# Power_Supply.net
KiCad netlist of a schematic drawn in Altium Designer
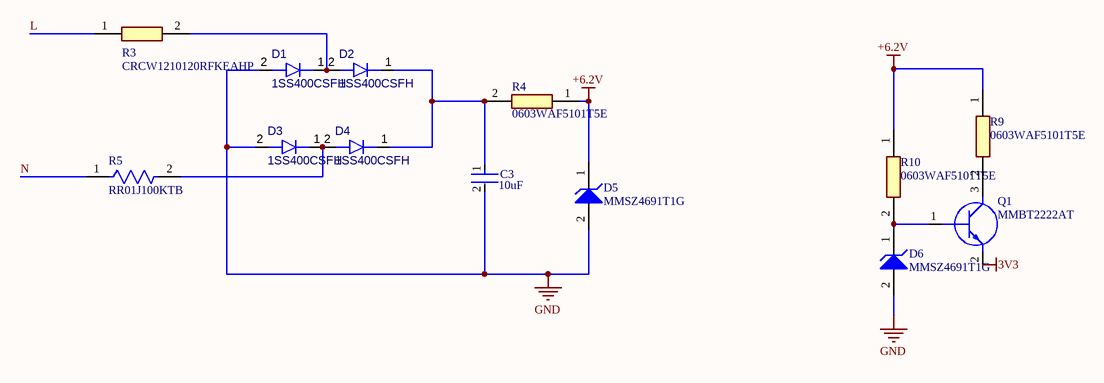
[diagram p0: Power Supply.SchDoc]

(export (version "E")
  (design (tool "Eeschema 10.0.6"))
  (components
    (comp (ref "C3")
      (value "1206YD106KAT2A")
      (footprint "FP-1206-L_3_2_0_2-W_1_6_0-IPC_B")
      (description "General Purpose Ceramic Capacitor, 1206, 10uF, 10%, X5R, 15%, 16V")
      (fields
        (field (name "TOLERANCE") "10%")
        (field (name "CAPACITANCE") "10uF")
        (field (name "VOLTAGE") "16V")
      )
      (libsource (lib "Altium Content Vault") (part "02cd4be3c70576c341d710602a673aa"))
    )
    (comp (ref "D1")
      (value "1SS400CSFH")
      (footprint "ROHM-VMN2-2_V")
      (description "Switching Diode (High Speed Switching), 80 V, 100 mA, 2-Pin SOD-923, RoHS, Tape and Reel")
      (libsource (lib "University of Moratuwa") (part "D-KA-2"))
    )
    (comp (ref "D2")
      (value "1SS400CSFH")
      (footprint "ROHM-VMN2-2_V")
      (description "Switching Diode (High Speed Switching), 80 V, 100 mA, 2-Pin SOD-923, RoHS, Tape and Reel")
      (libsource (lib "University of Moratuwa") (part "D-KA-2"))
    )
    (comp (ref "D3")
      (value "1SS400CSFH")
      (footprint "ROHM-VMN2-2_V")
      (description "Switching Diode (High Speed Switching), 80 V, 100 mA, 2-Pin SOD-923, RoHS, Tape and Reel")
      (libsource (lib "University of Moratuwa") (part "D-KA-2"))
    )
    (comp (ref "D4")
      (value "1SS400CSFH")
      (footprint "ROHM-VMN2-2_V")
      (description "Switching Diode (High Speed Switching), 80 V, 100 mA, 2-Pin SOD-923, RoHS, Tape and Reel")
      (libsource (lib "University of Moratuwa") (part "D-KA-2"))
    )
    (comp (ref "D5")
      (value "MMSZ4691T1G")
      (footprint "ONSC-SOD-123-2-425-04_V")
      (description "Zener Voltage Regulator, 500 mW, 2-Pin SOD-123, Pb-Free, Tape and Reel")
      (fields (field (name "MANUFACTURER") "On Semiconductor"))
      (libsource (lib "Altium Content Vault") (part "ONSC-K1A2-2"))
    )
    (comp (ref "D6")
      (value "MMSZ4691T1G")
      (footprint "ONSC-SOD-123-2-425-04_V")
      (description "Zener Voltage Regulator, 500 mW, 2-Pin SOD-123, Pb-Free, Tape and Reel")
      (fields (field (name "MANUFACTURER") "On Semiconductor"))
      (libsource (lib "Altium Content Vault") (part "ONSC-K1A2-2"))
    )
    (comp (ref "Q1")
      (value "MMBT2222AT")
      (footprint "SamacSys:SOTFL50P160X78-3N")
      (description "Transistor BJT NPN")
      (fields (field (name "MOUSER PART NUMBER") "512-MMBT2222AT"))
      (libsource (lib "*") (part "MMBT2222AT"))
    )
    (comp (ref "R3")
      (value "CRCW1210120RFKEAHP")
      (footprint "SamacSys:RESC3225X70N")
      (description "Resistor")
      (fields (field (name "MOUSER PART NUMBER") "71-CRCW1210120RFKEAH"))
      (libsource (lib "*") (part "CRCW1210120RFKEAHP"))
    )
    (comp (ref "R4")
      (value "0603WAF5101T5E")
      (footprint "SamacSys:RESC1608X55N")
      (description "Resistor")
      (libsource (lib "") (part "0603WAF5101T5E_1"))
    )
    (comp (ref "R5")
      (value "RR01J100KTB")
      (footprint "FP-RR01-MFG")
      (description "RES 100K OHM 5% 1W AXIAL")
      (fields (field (name "TOLERANCE") "5%"))
      (libsource (lib "Altium Content Vault") (part "1029c3af85768c4190bb7ad29bc67b5"))
    )
    (comp (ref "R9")
      (value "0603WAF5101T5E")
      (footprint "SamacSys:RESC1608X55N")
      (description "Resistor")
      (libsource (lib "*") (part "0603WAF5101T5E"))
    )
    (comp (ref "R10")
      (value "0603WAF5101T5E")
      (footprint "SamacSys:RESC1608X55N")
      (description "Resistor")
      (libsource (lib "*") (part "0603WAF5101T5E"))
    )
  )
  (nets
    (net (code "1") (name "+6.2V") (class "Default")
      (node (ref "D5") (pin "1") (pinfunction "K_1") (pintype "passive"))
      (node (ref "R10") (pin "1") (pinfunction "1_1") (pintype "passive"))
      (node (ref "R4") (pin "1") (pinfunction "1_1") (pintype "passive"))
      (node (ref "R9") (pin "1") (pinfunction "1_1") (pintype "passive"))
    )
    (net (code "2") (name "/L") (class "Default")
      (node (ref "R3") (pin "1") (pinfunction "1_1") (pintype "passive"))
    )
    (net (code "3") (name "/N") (class "Default")
      (node (ref "R5") (pin "1") (pinfunction "1_1") (pintype "passive"))
    )
    (net (code "4") (name "3V3") (class "Default")
      (node (ref "Q1") (pin "2") (pinfunction "E_2") (pintype "passive"))
    )
    (net (code "5") (name "GND") (class "Default")
      (node (ref "C3") (pin "2") (pinfunction "2_2") (pintype "passive"))
      (node (ref "D1") (pin "2") (pinfunction "A_2") (pintype "passive"))
      (node (ref "D3") (pin "2") (pinfunction "A_2") (pintype "passive"))
      (node (ref "D5") (pin "2") (pinfunction "A_2") (pintype "passive"))
      (node (ref "D6") (pin "2") (pinfunction "A_2") (pintype "passive"))
    )
    (net (code "6") (name "Net-(D1-K)") (class "Default")
      (node (ref "D1") (pin "1") (pinfunction "K_1") (pintype "passive"))
      (node (ref "D2") (pin "2") (pinfunction "A_2") (pintype "passive"))
      (node (ref "R3") (pin "2") (pinfunction "2_2") (pintype "passive"))
    )
    (net (code "7") (name "Net-(D2-K)") (class "Default")
      (node (ref "C3") (pin "1") (pinfunction "1_1") (pintype "passive"))
      (node (ref "D2") (pin "1") (pinfunction "K_1") (pintype "passive"))
      (node (ref "D4") (pin "1") (pinfunction "K_1") (pintype "passive"))
      (node (ref "R4") (pin "2") (pinfunction "2_2") (pintype "passive"))
    )
    (net (code "8") (name "Net-(D3-K)") (class "Default")
      (node (ref "D3") (pin "1") (pinfunction "K_1") (pintype "passive"))
      (node (ref "D4") (pin "2") (pinfunction "A_2") (pintype "passive"))
      (node (ref "R5") (pin "2") (pinfunction "2_2") (pintype "passive"))
    )
    (net (code "9") (name "Net-(D6-K)") (class "Default")
      (node (ref "D6") (pin "1") (pinfunction "K_1") (pintype "passive"))
      (node (ref "Q1") (pin "1") (pinfunction "B_1") (pintype "passive"))
      (node (ref "R10") (pin "2") (pinfunction "2_2") (pintype "passive"))
    )
    (net (code "10") (name "Net-(Q1-C)") (class "Default")
      (node (ref "Q1") (pin "3") (pinfunction "C_3") (pintype "passive"))
      (node (ref "R9") (pin "2") (pinfunction "2_2") (pintype "passive"))
    )
  )
)
